# amc7135-20mm-RGBW-led-driver-mk-1_0.net
KiCad netlist of a schematic drawn in EAGLE
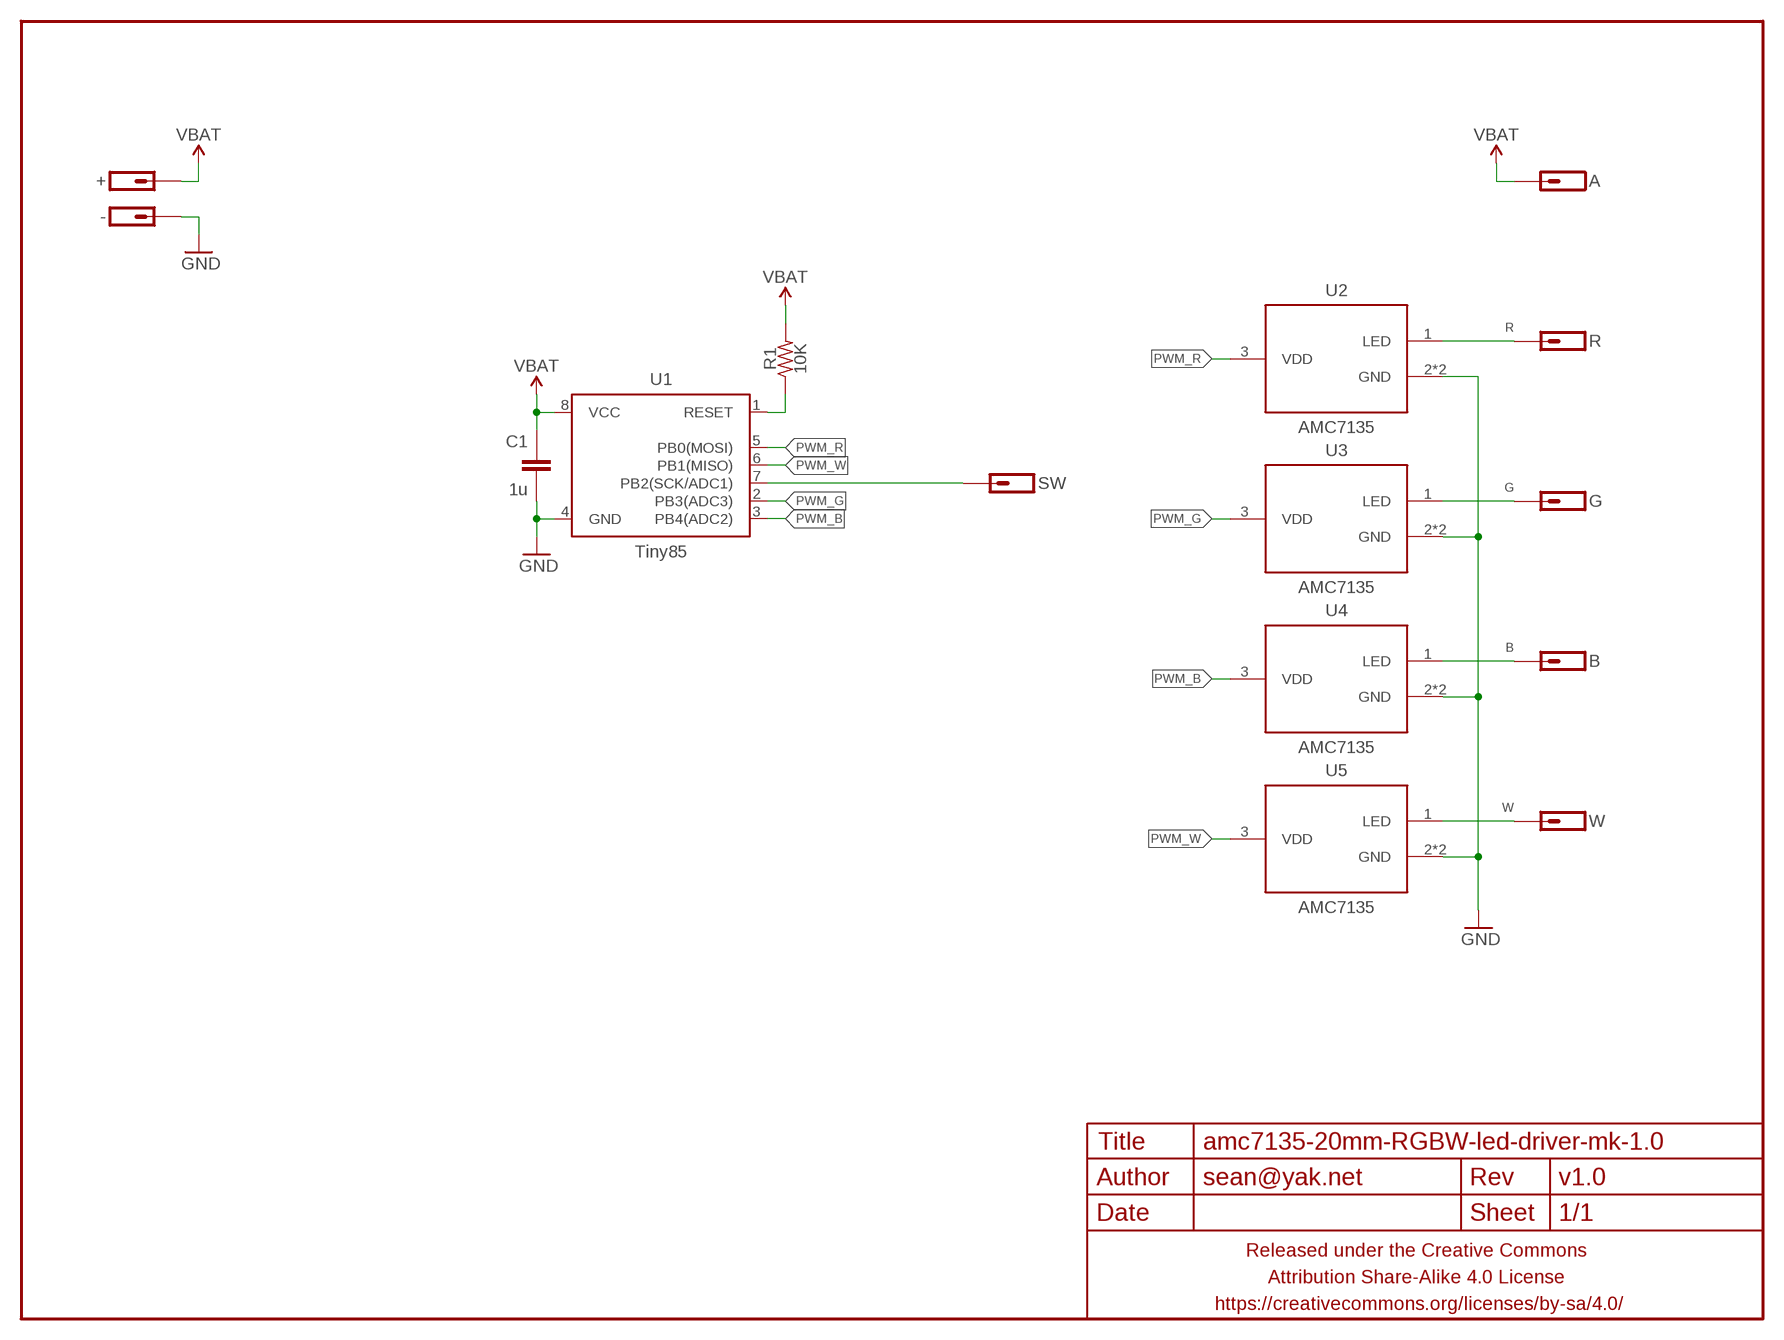
[diagram p0: schematic, sheet 1]

(export (version "E")
  (design (tool "Eeschema 10.0.6"))
  (components
    (comp (ref "+")
      (value "M01NOSTOP-CANTSTOP-DONTKNOWHOWTOSTOP")
      (footprint "eagle-import:1X01_SMD_NOSTOP_NOSILK")
      (libsource (lib "eagle-import") (part "M01NOSTOP-CANTSTOP-DONTKNOWHOWTOSTOP"))
    )
    (comp (ref "-")
      (value "M01NOT-A-VIA-NOPE")
      (footprint "eagle-import:1X01_NOSILK_NOSTOP")
      (libsource (lib "eagle-import") (part "M01NOT-A-VIA-NOPE"))
    )
    (comp (ref "A")
      (value "M01PTH-1MM-CIR-NS")
      (footprint "eagle-import:1X01-1MM-CIR-NS")
      (libsource (lib "eagle-import") (part "M01PTH-1MM-CIR-NS"))
    )
    (comp (ref "B")
      (value "M01PTH-1MM-CIR-NS")
      (footprint "eagle-import:1X01-1MM-CIR-NS")
      (libsource (lib "eagle-import") (part "M01PTH-1MM-CIR-NS"))
    )
    (comp (ref "C1")
      (value "1u")
      (footprint "eagle-import:C0603-TIGHTER")
      (libsource (lib "eagle-import") (part "CAPACITOR-CERAMICC0603-TIGHTER"))
    )
    (comp (ref "FRAME1")
      (value "FRAME-LETTERNO_PACKAGE")
      (footprint "eagle-import:DUMMY")
      (fields (field (name "DESIGNER") "sean@yak.net") (field (name "VERSION") "v1.0"))
      (libsource (lib "eagle-import") (part "FRAME-LETTERNO_PACKAGE"))
    )
    (comp (ref "G")
      (value "M01PTH-1MM-CIR-NS")
      (footprint "eagle-import:1X01-1MM-CIR-NS")
      (libsource (lib "eagle-import") (part "M01PTH-1MM-CIR-NS"))
    )
    (comp (ref "R")
      (value "M01PTH-1MM-CIR-NS")
      (footprint "eagle-import:1X01-1MM-CIR-NS")
      (libsource (lib "eagle-import") (part "M01PTH-1MM-CIR-NS"))
    )
    (comp (ref "R1")
      (value "10K")
      (footprint "eagle-import:R0603-TIGHTER")
      (libsource (lib "eagle-import") (part "RESISTORR0603-TIGHTER"))
    )
    (comp (ref "SW")
      (value "M01PTH-0.8MM")
      (footprint "eagle-import:1X01-0.8MM")
      (libsource (lib "eagle-import") (part "M01PTH-0.8MM"))
    )
    (comp (ref "U1")
      (value "Tiny85")
      (footprint "eagle-import:SO08-EIAJ")
      (libsource (lib "eagle-import") (part "ATTINY45TINY85-20-SOICW"))
    )
    (comp (ref "U2")
      (value "AMC7135")
      (footprint "eagle-import:SOT89")
      (libsource (lib "eagle-import") (part "AMC7135SOT-89"))
    )
    (comp (ref "U3")
      (value "AMC7135")
      (footprint "eagle-import:SOT89")
      (libsource (lib "eagle-import") (part "AMC7135SOT-89"))
    )
    (comp (ref "U4")
      (value "AMC7135")
      (footprint "eagle-import:SOT89")
      (libsource (lib "eagle-import") (part "AMC7135SOT-89"))
    )
    (comp (ref "U5")
      (value "AMC7135")
      (footprint "eagle-import:SOT89")
      (libsource (lib "eagle-import") (part "AMC7135SOT-89"))
    )
    (comp (ref "W")
      (value "M01PTH-1MM-CIR-NS")
      (footprint "eagle-import:1X01-1MM-CIR-NS")
      (libsource (lib "eagle-import") (part "M01PTH-1MM-CIR-NS"))
    )
  )
  (nets
    (net (code "1") (name "/B") (class "Default")
      (node (ref "B") (pin "1") (pinfunction "1_1") (pintype "passive"))
      (node (ref "U4") (pin "1") (pinfunction "LED_1") (pintype "bidirectional"))
    )
    (net (code "2") (name "/G") (class "Default")
      (node (ref "G") (pin "1") (pinfunction "1_1") (pintype "passive"))
      (node (ref "U3") (pin "1") (pinfunction "LED_1") (pintype "bidirectional"))
    )
    (net (code "3") (name "/R") (class "Default")
      (node (ref "R") (pin "1") (pinfunction "1_1") (pintype "passive"))
      (node (ref "U2") (pin "1") (pinfunction "LED_1") (pintype "bidirectional"))
    )
    (net (code "4") (name "/W") (class "Default")
      (node (ref "U5") (pin "1") (pinfunction "LED_1") (pintype "bidirectional"))
      (node (ref "W") (pin "1") (pinfunction "1_1") (pintype "passive"))
    )
    (net (code "5") (name "GND") (class "Default")
      (node (ref "-") (pin "P$1") (pinfunction "1_P$1") (pintype "passive"))
      (node (ref "C1") (pin "2") (pinfunction "2_2") (pintype "passive"))
      (node (ref "U1") (pin "4") (pinfunction "GND_4") (pintype "bidirectional"))
      (node (ref "U2") (pin "2") (pinfunction "GND_2") (pintype "bidirectional"))
      (node (ref "U2") (pin "4") (pinfunction "GND_4") (pintype "bidirectional"))
      (node (ref "U3") (pin "2") (pinfunction "GND_2") (pintype "bidirectional"))
      (node (ref "U3") (pin "4") (pinfunction "GND_4") (pintype "bidirectional"))
      (node (ref "U4") (pin "2") (pinfunction "GND_2") (pintype "bidirectional"))
      (node (ref "U4") (pin "4") (pinfunction "GND_4") (pintype "bidirectional"))
      (node (ref "U5") (pin "2") (pinfunction "GND_2") (pintype "bidirectional"))
      (node (ref "U5") (pin "4") (pinfunction "GND_4") (pintype "bidirectional"))
    )
    (net (code "6") (name "Net-(U1-PB2(SCK{slash}ADC1))") (class "Default")
      (node (ref "SW") (pin "1") (pinfunction "1_1") (pintype "passive"))
      (node (ref "U1") (pin "7") (pinfunction "PB2(SCK/ADC1)_7") (pintype "bidirectional"))
    )
    (net (code "7") (name "Net-(U1-RESET)") (class "Default")
      (node (ref "R1") (pin "1") (pinfunction "1_1") (pintype "passive"))
      (node (ref "U1") (pin "1") (pinfunction "RESET_1") (pintype "bidirectional"))
    )
    (net (code "8") (name "PWM_B") (class "Default")
      (node (ref "U1") (pin "3") (pinfunction "PB4(ADC2)_3") (pintype "bidirectional"))
      (node (ref "U4") (pin "3") (pinfunction "VDD_3") (pintype "bidirectional"))
    )
    (net (code "9") (name "PWM_G") (class "Default")
      (node (ref "U1") (pin "2") (pinfunction "PB3(ADC3)_2") (pintype "bidirectional"))
      (node (ref "U3") (pin "3") (pinfunction "VDD_3") (pintype "bidirectional"))
    )
    (net (code "10") (name "PWM_R") (class "Default")
      (node (ref "U1") (pin "5") (pinfunction "PB0(MOSI)_5") (pintype "bidirectional"))
      (node (ref "U2") (pin "3") (pinfunction "VDD_3") (pintype "bidirectional"))
    )
    (net (code "11") (name "PWM_W") (class "Default")
      (node (ref "U1") (pin "6") (pinfunction "PB1(MISO)_6") (pintype "bidirectional"))
      (node (ref "U5") (pin "3") (pinfunction "VDD_3") (pintype "bidirectional"))
    )
    (net (code "12") (name "VBAT") (class "Default")
      (node (ref "+") (pin "1") (pinfunction "1_1") (pintype "passive"))
      (node (ref "A") (pin "1") (pinfunction "1_1") (pintype "passive"))
      (node (ref "C1") (pin "1") (pinfunction "1_1") (pintype "passive"))
      (node (ref "R1") (pin "2") (pinfunction "2_2") (pintype "passive"))
      (node (ref "U1") (pin "8") (pinfunction "VCC_8") (pintype "bidirectional"))
    )
  )
)
